# 2164_svf_breakout_planes.net
KiCad netlist of a schematic drawn in EAGLE
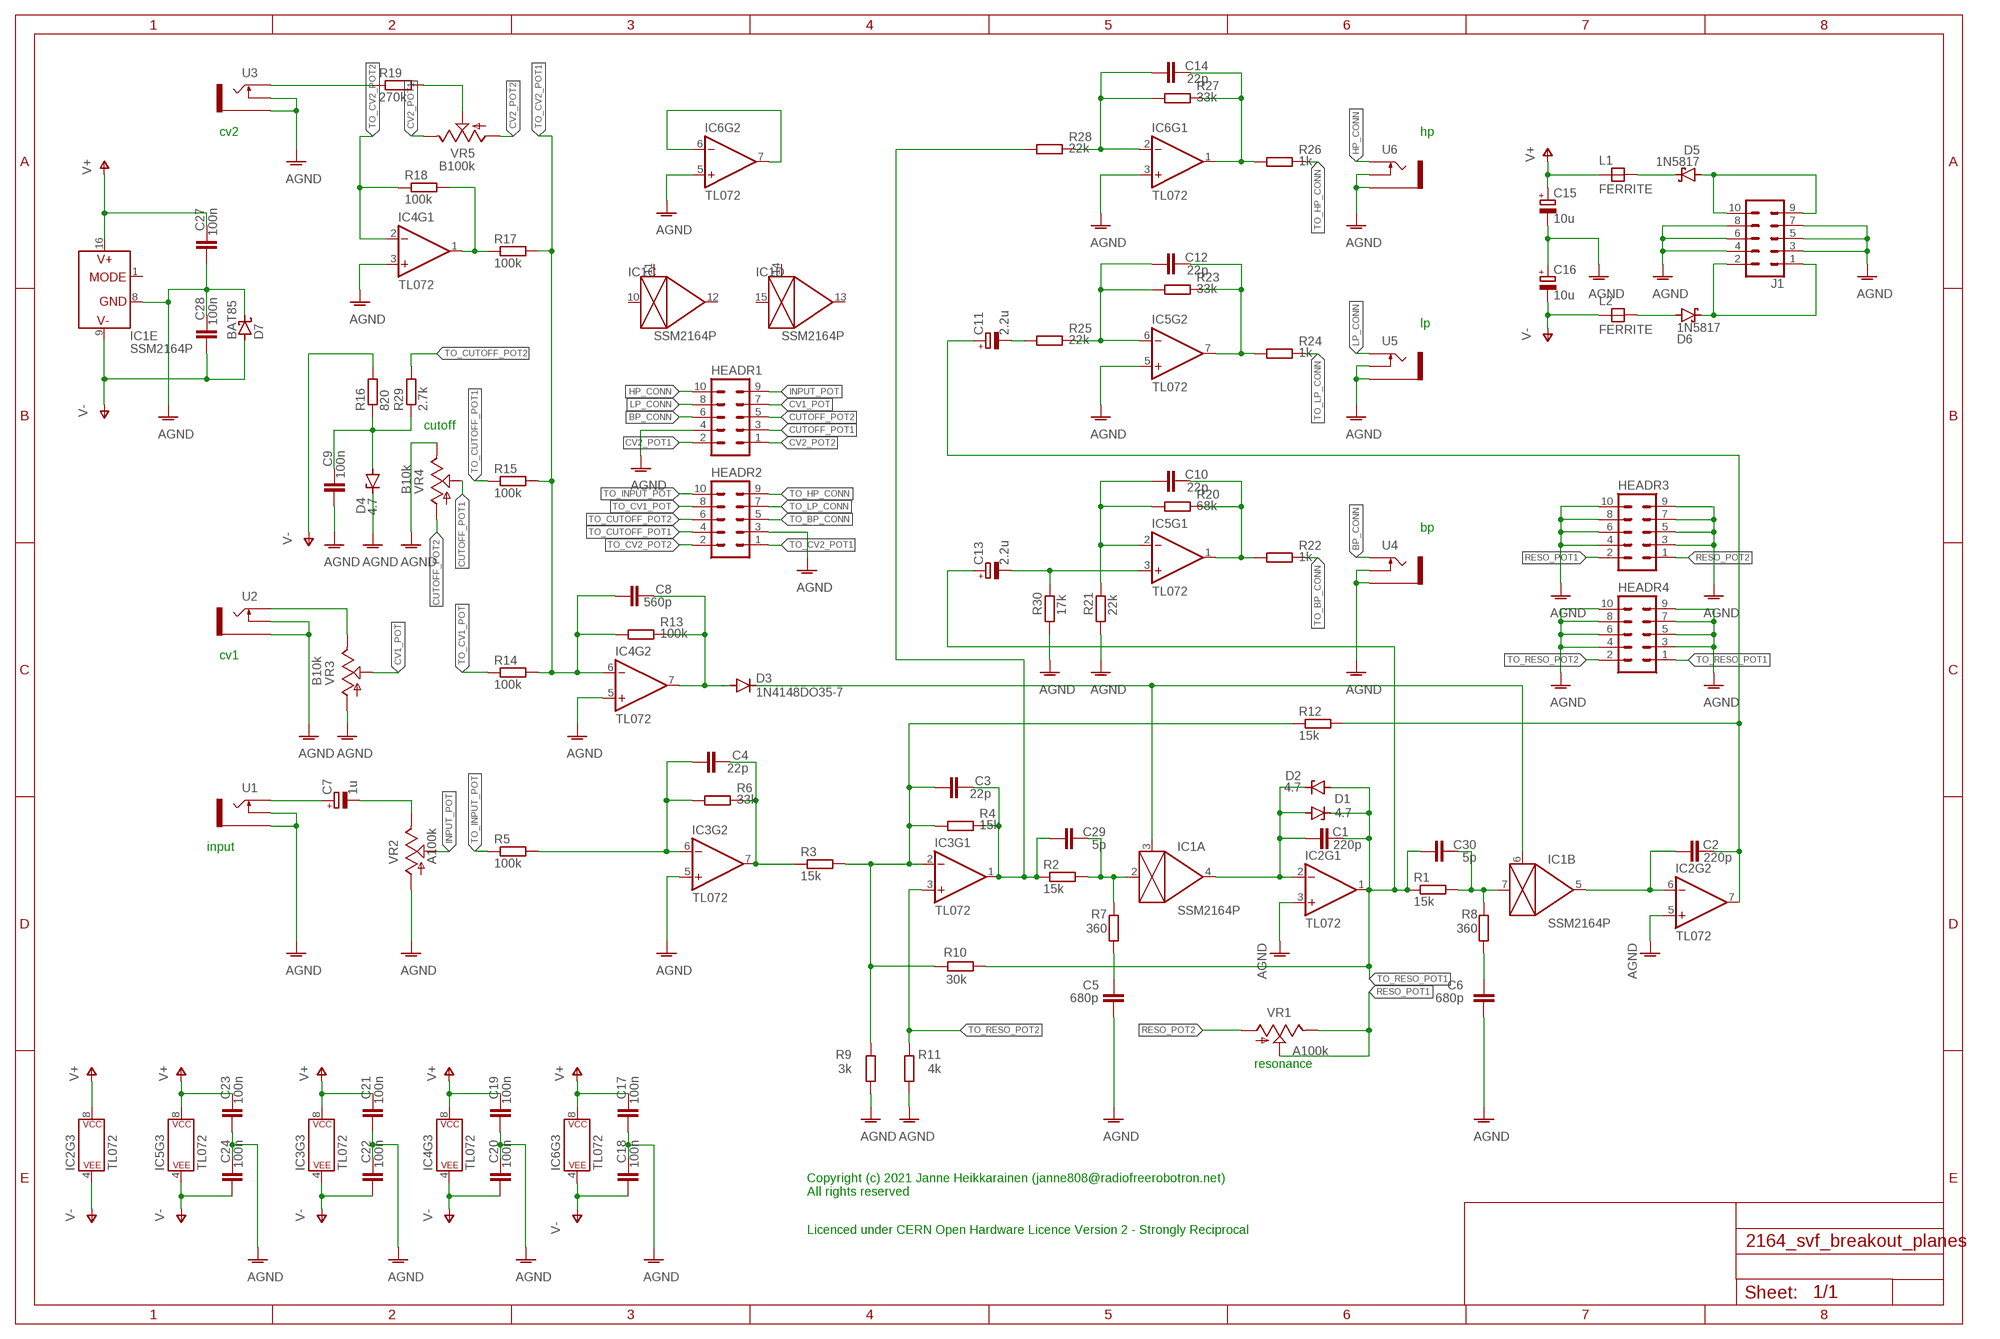
[diagram p0: schematic, sheet 1]

(export (version "E")
  (design (tool "Eeschema 10.0.6"))
  (components
    (comp (ref "C1")
      (value "220p")
      (footprint "eagle-import:C050-025X075")
      (libsource (lib "eagle-import") (part "C-EU050-025X075"))
    )
    (comp (ref "C2")
      (value "220p")
      (footprint "eagle-import:C050-025X075")
      (libsource (lib "eagle-import") (part "C-EU050-025X075"))
    )
    (comp (ref "C3")
      (value "22p")
      (footprint "eagle-import:C050-025X075")
      (libsource (lib "eagle-import") (part "C-EU050-025X075"))
    )
    (comp (ref "C4")
      (value "22p")
      (footprint "eagle-import:C050-025X075")
      (libsource (lib "eagle-import") (part "C-EU050-025X075"))
    )
    (comp (ref "C5")
      (value "680p")
      (footprint "eagle-import:C050-025X075")
      (libsource (lib "eagle-import") (part "C-EU050-025X075"))
    )
    (comp (ref "C6")
      (value "680p")
      (footprint "eagle-import:C050-025X075")
      (libsource (lib "eagle-import") (part "C-EU050-025X075"))
    )
    (comp (ref "C7")
      (value "1u")
      (footprint "eagle-import:E2,5-6E")
      (libsource (lib "eagle-import") (part "CPOL-EUE2,5-6E"))
    )
    (comp (ref "C8")
      (value "560p")
      (footprint "eagle-import:C050-025X075")
      (libsource (lib "eagle-import") (part "C-EU050-025X075"))
    )
    (comp (ref "C9")
      (value "100n")
      (footprint "eagle-import:C050-025X075")
      (libsource (lib "eagle-import") (part "C-EU050-025X075"))
    )
    (comp (ref "C10")
      (value "22p")
      (footprint "eagle-import:C050-025X075")
      (libsource (lib "eagle-import") (part "C-EU050-025X075"))
    )
    (comp (ref "C11")
      (value "2.2u")
      (footprint "eagle-import:E2,5-6E")
      (libsource (lib "eagle-import") (part "CPOL-EUE2,5-6E"))
    )
    (comp (ref "C12")
      (value "22p")
      (footprint "eagle-import:C050-025X075")
      (libsource (lib "eagle-import") (part "C-EU050-025X075"))
    )
    (comp (ref "C13")
      (value "2.2u")
      (footprint "eagle-import:E2,5-6E")
      (libsource (lib "eagle-import") (part "CPOL-EUE2,5-6E"))
    )
    (comp (ref "C14")
      (value "22p")
      (footprint "eagle-import:C050-025X075")
      (libsource (lib "eagle-import") (part "C-EU050-025X075"))
    )
    (comp (ref "C15")
      (value "10u")
      (footprint "eagle-import:E2,5-6E")
      (libsource (lib "eagle-import") (part "CPOL-EUE2,5-6E"))
    )
    (comp (ref "C16")
      (value "10u")
      (footprint "eagle-import:E2,5-6E")
      (libsource (lib "eagle-import") (part "CPOL-EUE2,5-6E"))
    )
    (comp (ref "C17")
      (value "100n")
      (footprint "eagle-import:C050-025X075")
      (libsource (lib "eagle-import") (part "C-EU050-025X075"))
    )
    (comp (ref "C18")
      (value "100n")
      (footprint "eagle-import:C050-025X075")
      (libsource (lib "eagle-import") (part "C-EU050-025X075"))
    )
    (comp (ref "C19")
      (value "100n")
      (footprint "eagle-import:C050-025X075")
      (libsource (lib "eagle-import") (part "C-EU050-025X075"))
    )
    (comp (ref "C20")
      (value "100n")
      (footprint "eagle-import:C050-025X075")
      (libsource (lib "eagle-import") (part "C-EU050-025X075"))
    )
    (comp (ref "C21")
      (value "100n")
      (footprint "eagle-import:C050-025X075")
      (libsource (lib "eagle-import") (part "C-EU050-025X075"))
    )
    (comp (ref "C22")
      (value "100n")
      (footprint "eagle-import:C050-025X075")
      (libsource (lib "eagle-import") (part "C-EU050-025X075"))
    )
    (comp (ref "C23")
      (value "100n")
      (footprint "eagle-import:C050-025X075")
      (libsource (lib "eagle-import") (part "C-EU050-025X075"))
    )
    (comp (ref "C24")
      (value "100n")
      (footprint "eagle-import:C050-025X075")
      (libsource (lib "eagle-import") (part "C-EU050-025X075"))
    )
    (comp (ref "C27")
      (value "100n")
      (footprint "eagle-import:C050-025X075")
      (libsource (lib "eagle-import") (part "C-EU050-025X075"))
    )
    (comp (ref "C28")
      (value "100n")
      (footprint "eagle-import:C050-025X075")
      (libsource (lib "eagle-import") (part "C-EU050-025X075"))
    )
    (comp (ref "C29")
      (value "5p")
      (footprint "eagle-import:C050-025X075")
      (libsource (lib "eagle-import") (part "C-EU050-025X075"))
    )
    (comp (ref "C30")
      (value "5p")
      (footprint "eagle-import:C050-025X075")
      (libsource (lib "eagle-import") (part "C-EU050-025X075"))
    )
    (comp (ref "D1")
      (value "4.7")
      (footprint "eagle-import:DO34Z7")
      (libsource (lib "eagle-import") (part "ZENER-DIODEDO34-7"))
    )
    (comp (ref "D2")
      (value "4.7")
      (footprint "eagle-import:DO34Z7")
      (libsource (lib "eagle-import") (part "ZENER-DIODEDO34-7"))
    )
    (comp (ref "D3")
      (value "1N4148DO35-7")
      (footprint "eagle-import:DO35-7")
      (libsource (lib "eagle-import") (part "1N4148DO35-7"))
    )
    (comp (ref "D4")
      (value "4.7")
      (footprint "eagle-import:DO34Z7")
      (libsource (lib "eagle-import") (part "ZENER-DIODEDO34-7"))
    )
    (comp (ref "D5")
      (value "1N5817")
      (footprint "eagle-import:DO35-7")
      (libsource (lib "eagle-import") (part "SCHOTTKY-DIODEDO35-7"))
    )
    (comp (ref "D6")
      (value "1N5817")
      (footprint "eagle-import:DO35-7")
      (libsource (lib "eagle-import") (part "SCHOTTKY-DIODEDO35-7"))
    )
    (comp (ref "D7")
      (value "BAT85")
      (footprint "eagle-import:DO35-7")
      (libsource (lib "eagle-import") (part "SCHOTTKY-DIODEDO35-7"))
    )
    (comp (ref "HEADR1")
      (value "10PIN_BACKSIDE")
      (footprint "eagle-import:10PIN_BACKSIDE")
      (libsource (lib "eagle-import") (part "10PIN_BACKSIDE"))
    )
    (comp (ref "HEADR2")
      (value "10PIN_BACKSIDE")
      (footprint "eagle-import:10PIN_BACKSIDE")
      (libsource (lib "eagle-import") (part "10PIN_BACKSIDE"))
    )
    (comp (ref "HEADR3")
      (value "10PIN_BACKSIDE")
      (footprint "eagle-import:10PIN_BACKSIDE")
      (libsource (lib "eagle-import") (part "10PIN_BACKSIDE"))
    )
    (comp (ref "HEADR4")
      (value "10PIN_BACKSIDE")
      (footprint "eagle-import:10PIN_BACKSIDE")
      (libsource (lib "eagle-import") (part "10PIN_BACKSIDE"))
    )
    (comp (ref "IC1")
      (value "SSM2164P")
      (footprint "eagle-import:DIL16")
      (libsource (lib "eagle-import") (part "SSM2164P"))
    )
    (comp (ref "IC2")
      (value "TL072")
      (footprint "eagle-import:DIP08")
      (libsource (lib "eagle-import") (part "OPAMP-DUALDIP"))
    )
    (comp (ref "IC3")
      (value "TL072")
      (footprint "eagle-import:DIP08")
      (libsource (lib "eagle-import") (part "OPAMP-DUALDIP"))
    )
    (comp (ref "IC4")
      (value "TL072")
      (footprint "eagle-import:DIP08")
      (libsource (lib "eagle-import") (part "OPAMP-DUALDIP"))
    )
    (comp (ref "IC5")
      (value "TL072")
      (footprint "eagle-import:DIP08")
      (libsource (lib "eagle-import") (part "OPAMP-DUALDIP"))
    )
    (comp (ref "IC6")
      (value "TL072")
      (footprint "eagle-import:DIP08")
      (libsource (lib "eagle-import") (part "OPAMP-DUALDIP"))
    )
    (comp (ref "J1")
      (value "CONN_05X2SHD")
      (footprint "eagle-import:2X5-SHROUDED")
      (libsource (lib "eagle-import") (part "CONN_05X2SHD"))
    )
    (comp (ref "L1")
      (value "FERRITE")
      (footprint "eagle-import:FB-085")
      (libsource (lib "eagle-import") (part "FB-085"))
    )
    (comp (ref "L2")
      (value "FERRITE")
      (footprint "eagle-import:FB-085")
      (libsource (lib "eagle-import") (part "FB-085"))
    )
    (comp (ref "R1")
      (value "15k")
      (footprint "eagle-import:0207_2V")
      (libsource (lib "eagle-import") (part "R-EU_0207/2V"))
    )
    (comp (ref "R2")
      (value "15k")
      (footprint "eagle-import:0207_2V")
      (libsource (lib "eagle-import") (part "R-EU_0207/2V"))
    )
    (comp (ref "R3")
      (value "15k")
      (footprint "eagle-import:0207_2V")
      (libsource (lib "eagle-import") (part "R-EU_0207/2V"))
    )
    (comp (ref "R4")
      (value "15k")
      (footprint "eagle-import:0207_2V")
      (libsource (lib "eagle-import") (part "R-EU_0207/2V"))
    )
    (comp (ref "R5")
      (value "100k")
      (footprint "eagle-import:0207_2V")
      (libsource (lib "eagle-import") (part "R-EU_0207/2V"))
    )
    (comp (ref "R6")
      (value "33k")
      (footprint "eagle-import:0207_2V")
      (libsource (lib "eagle-import") (part "R-EU_0207/2V"))
    )
    (comp (ref "R7")
      (value "360")
      (footprint "eagle-import:0207_2V")
      (libsource (lib "eagle-import") (part "R-EU_0207/2V"))
    )
    (comp (ref "R8")
      (value "360")
      (footprint "eagle-import:0207_2V")
      (libsource (lib "eagle-import") (part "R-EU_0207/2V"))
    )
    (comp (ref "R9")
      (value "3k")
      (footprint "eagle-import:0207_2V")
      (libsource (lib "eagle-import") (part "R-EU_0207/2V"))
    )
    (comp (ref "R10")
      (value "30k")
      (footprint "eagle-import:0207_2V")
      (libsource (lib "eagle-import") (part "R-EU_0207/2V"))
    )
    (comp (ref "R11")
      (value "4k")
      (footprint "eagle-import:0207_2V")
      (libsource (lib "eagle-import") (part "R-EU_0207/2V"))
    )
    (comp (ref "R12")
      (value "15k")
      (footprint "eagle-import:0207_2V")
      (libsource (lib "eagle-import") (part "R-EU_0207/2V"))
    )
    (comp (ref "R13")
      (value "100k")
      (footprint "eagle-import:0207_2V")
      (libsource (lib "eagle-import") (part "R-EU_0207/2V"))
    )
    (comp (ref "R14")
      (value "100k")
      (footprint "eagle-import:0207_2V")
      (libsource (lib "eagle-import") (part "R-EU_0207/2V"))
    )
    (comp (ref "R15")
      (value "100k")
      (footprint "eagle-import:0207_2V")
      (libsource (lib "eagle-import") (part "R-EU_0207/2V"))
    )
    (comp (ref "R16")
      (value "820")
      (footprint "eagle-import:0207_2V")
      (libsource (lib "eagle-import") (part "R-EU_0207/2V"))
    )
    (comp (ref "R17")
      (value "100k")
      (footprint "eagle-import:0207_2V")
      (libsource (lib "eagle-import") (part "R-EU_0207/2V"))
    )
    (comp (ref "R18")
      (value "100k")
      (footprint "eagle-import:0207_2V")
      (libsource (lib "eagle-import") (part "R-EU_0207/2V"))
    )
    (comp (ref "R19")
      (value "270k")
      (footprint "eagle-import:0207_2V")
      (libsource (lib "eagle-import") (part "R-EU_0207/2V"))
    )
    (comp (ref "R20")
      (value "68k")
      (footprint "eagle-import:0207_2V")
      (libsource (lib "eagle-import") (part "R-EU_0207/2V"))
    )
    (comp (ref "R21")
      (value "22k")
      (footprint "eagle-import:0207_2V")
      (libsource (lib "eagle-import") (part "R-EU_0207/2V"))
    )
    (comp (ref "R22")
      (value "1k")
      (footprint "eagle-import:0207_2V")
      (libsource (lib "eagle-import") (part "R-EU_0207/2V"))
    )
    (comp (ref "R23")
      (value "33k")
      (footprint "eagle-import:0207_2V")
      (libsource (lib "eagle-import") (part "R-EU_0207/2V"))
    )
    (comp (ref "R24")
      (value "1k")
      (footprint "eagle-import:0207_2V")
      (libsource (lib "eagle-import") (part "R-EU_0207/2V"))
    )
    (comp (ref "R25")
      (value "22k")
      (footprint "eagle-import:0207_2V")
      (libsource (lib "eagle-import") (part "R-EU_0207/2V"))
    )
    (comp (ref "R26")
      (value "1k")
      (footprint "eagle-import:0207_2V")
      (libsource (lib "eagle-import") (part "R-EU_0207/2V"))
    )
    (comp (ref "R27")
      (value "33k")
      (footprint "eagle-import:0207_2V")
      (libsource (lib "eagle-import") (part "R-EU_0207/2V"))
    )
    (comp (ref "R28")
      (value "22k")
      (footprint "eagle-import:0207_2V")
      (libsource (lib "eagle-import") (part "R-EU_0207/2V"))
    )
    (comp (ref "R29")
      (value "2.7k")
      (footprint "eagle-import:0207_2V")
      (libsource (lib "eagle-import") (part "R-EU_0207/2V"))
    )
    (comp (ref "R30")
      (value "17k")
      (footprint "eagle-import:0207_2V")
      (libsource (lib "eagle-import") (part "R-EU_0207/2V"))
    )
    (comp (ref "U1")
      (value "THONKICONNNEW")
      (footprint "eagle-import:WQP-PJ301M-12_JACK")
      (libsource (lib "eagle-import") (part "THONKICONNNEW"))
    )
    (comp (ref "U2")
      (value "THONKICONNNEW")
      (footprint "eagle-import:WQP-PJ301M-12_JACK")
      (libsource (lib "eagle-import") (part "THONKICONNNEW"))
    )
    (comp (ref "U3")
      (value "THONKICONNNEW")
      (footprint "eagle-import:WQP-PJ301M-12_JACK")
      (libsource (lib "eagle-import") (part "THONKICONNNEW"))
    )
    (comp (ref "U4")
      (value "THONKICONNNEW")
      (footprint "eagle-import:WQP-PJ301M-12_JACK")
      (libsource (lib "eagle-import") (part "THONKICONNNEW"))
    )
    (comp (ref "U5")
      (value "THONKICONNNEW")
      (footprint "eagle-import:WQP-PJ301M-12_JACK")
      (libsource (lib "eagle-import") (part "THONKICONNNEW"))
    )
    (comp (ref "U6")
      (value "THONKICONNNEW")
      (footprint "eagle-import:WQP-PJ301M-12_JACK")
      (libsource (lib "eagle-import") (part "THONKICONNNEW"))
    )
    (comp (ref "VR1")
      (value "A100k")
      (footprint "eagle-import:9MM_SNAP-IN_POT")
      (libsource (lib "eagle-import") (part "9MM_SNAP-IN_POT_"))
    )
    (comp (ref "VR2")
      (value "A100k")
      (footprint "eagle-import:9MM_SNAP-IN_POT")
      (libsource (lib "eagle-import") (part "9MM_SNAP-IN_POT_"))
    )
    (comp (ref "VR3")
      (value "B10k")
      (footprint "eagle-import:9MM_SNAP-IN_POT")
      (libsource (lib "eagle-import") (part "9MM_SNAP-IN_POT_"))
    )
    (comp (ref "VR4")
      (value "B10k")
      (footprint "eagle-import:9MM_SNAP-IN_POT")
      (libsource (lib "eagle-import") (part "9MM_SNAP-IN_POT_"))
    )
    (comp (ref "VR5")
      (value "B100k")
      (footprint "eagle-import:9MM_SNAP-IN_POT")
      (libsource (lib "eagle-import") (part "9MM_SNAP-IN_POT_"))
    )
  )
  (nets
    (net (code "1") (name "AGND") (class "Default")
      (node (ref "C15") (pin "-") (pinfunction "-_-") (pintype "passive"))
      (node (ref "C16") (pin "+") (pinfunction "+_+") (pintype "passive"))
      (node (ref "C17") (pin "1") (pinfunction "1_1") (pintype "passive"))
      (node (ref "C18") (pin "2") (pinfunction "2_2") (pintype "passive"))
      (node (ref "C19") (pin "1") (pinfunction "1_1") (pintype "passive"))
      (node (ref "C20") (pin "2") (pinfunction "2_2") (pintype "passive"))
      (node (ref "C21") (pin "1") (pinfunction "1_1") (pintype "passive"))
      (node (ref "C22") (pin "2") (pinfunction "2_2") (pintype "passive"))
      (node (ref "C23") (pin "1") (pinfunction "1_1") (pintype "passive"))
      (node (ref "C24") (pin "2") (pinfunction "2_2") (pintype "passive"))
      (node (ref "C27") (pin "1") (pinfunction "1_1") (pintype "passive"))
      (node (ref "C28") (pin "2") (pinfunction "2_2") (pintype "passive"))
      (node (ref "C5") (pin "1") (pinfunction "1_1") (pintype "passive"))
      (node (ref "C6") (pin "1") (pinfunction "1_1") (pintype "passive"))
      (node (ref "C9") (pin "1") (pinfunction "1_1") (pintype "passive"))
      (node (ref "D4") (pin "C") (pinfunction "C_C") (pintype "passive"))
      (node (ref "D7") (pin "C") (pinfunction "C_C") (pintype "passive"))
      (node (ref "HEADR1") (pin "4") (pinfunction "4_4") (pintype "passive"))
      (node (ref "HEADR2") (pin "3") (pinfunction "3_3") (pintype "passive"))
      (node (ref "HEADR3") (pin "10") (pinfunction "10_10") (pintype "passive"))
      (node (ref "HEADR3") (pin "3") (pinfunction "3_3") (pintype "passive"))
      (node (ref "HEADR3") (pin "4") (pinfunction "4_4") (pintype "passive"))
      (node (ref "HEADR3") (pin "5") (pinfunction "5_5") (pintype "passive"))
      (node (ref "HEADR3") (pin "6") (pinfunction "6_6") (pintype "passive"))
      (node (ref "HEADR3") (pin "7") (pinfunction "7_7") (pintype "passive"))
      (node (ref "HEADR3") (pin "8") (pinfunction "8_8") (pintype "passive"))
      (node (ref "HEADR3") (pin "9") (pinfunction "9_9") (pintype "passive"))
      (node (ref "HEADR4") (pin "10") (pinfunction "10_10") (pintype "passive"))
      (node (ref "HEADR4") (pin "3") (pinfunction "3_3") (pintype "passive"))
      (node (ref "HEADR4") (pin "4") (pinfunction "4_4") (pintype "passive"))
      (node (ref "HEADR4") (pin "5") (pinfunction "5_5") (pintype "passive"))
      (node (ref "HEADR4") (pin "6") (pinfunction "6_6") (pintype "passive"))
      (node (ref "HEADR4") (pin "7") (pinfunction "7_7") (pintype "passive"))
      (node (ref "HEADR4") (pin "8") (pinfunction "8_8") (pintype "passive"))
      (node (ref "HEADR4") (pin "9") (pinfunction "9_9") (pintype "passive"))
      (node (ref "IC1") (pin "8") (pinfunction "GND_8") (pintype "power_in"))
      (node (ref "IC2") (pin "3") (pinfunction "+IN_3") (pintype "input"))
      (node (ref "IC2") (pin "5") (pinfunction "+IN_5") (pintype "input"))
      (node (ref "IC3") (pin "5") (pinfunction "+IN_5") (pintype "input"))
      (node (ref "IC4") (pin "3") (pinfunction "+IN_3") (pintype "input"))
      (node (ref "IC4") (pin "5") (pinfunction "+IN_5") (pintype "input"))
      (node (ref "IC5") (pin "5") (pinfunction "+IN_5") (pintype "input"))
      (node (ref "IC6") (pin "3") (pinfunction "+IN_3") (pintype "input"))
      (node (ref "IC6") (pin "5") (pinfunction "+IN_5") (pintype "input"))
      (node (ref "J1") (pin "3") (pinfunction "3_3") (pintype "passive"))
      (node (ref "J1") (pin "4") (pinfunction "4_4") (pintype "passive"))
      (node (ref "J1") (pin "5") (pinfunction "5_5") (pintype "passive"))
      (node (ref "J1") (pin "6") (pinfunction "6_6") (pintype "passive"))
      (node (ref "J1") (pin "7") (pinfunction "7_7") (pintype "passive"))
      (node (ref "J1") (pin "8") (pinfunction "8_8") (pintype "passive"))
      (node (ref "R11") (pin "1") (pinfunction "1_1") (pintype "passive"))
      (node (ref "R21") (pin "1") (pinfunction "1_1") (pintype "passive"))
      (node (ref "R30") (pin "1") (pinfunction "1_1") (pintype "passive"))
      (node (ref "R9") (pin "1") (pinfunction "1_1") (pintype "passive"))
      (node (ref "U1") (pin "P$2_SWITCH") (pinfunction "SWITCH_P$2_SWITCH") (pintype "passive"))
      (node (ref "U1") (pin "P$3_SLEEVE") (pinfunction "SLEEVE_P$3_SLEEVE") (pintype "passive"))
      (node (ref "U2") (pin "P$2_SWITCH") (pinfunction "SWITCH_P$2_SWITCH") (pintype "passive"))
      (node (ref "U2") (pin "P$3_SLEEVE") (pinfunction "SLEEVE_P$3_SLEEVE") (pintype "passive"))
      (node (ref "U3") (pin "P$2_SWITCH") (pinfunction "SWITCH_P$2_SWITCH") (pintype "passive"))
      (node (ref "U3") (pin "P$3_SLEEVE") (pinfunction "SLEEVE_P$3_SLEEVE") (pintype "passive"))
      (node (ref "U4") (pin "P$2_SWITCH") (pinfunction "SWITCH_P$2_SWITCH") (pintype "passive"))
      (node (ref "U4") (pin "P$3_SLEEVE") (pinfunction "SLEEVE_P$3_SLEEVE") (pintype "passive"))
      (node (ref "U5") (pin "P$2_SWITCH") (pinfunction "SWITCH_P$2_SWITCH") (pintype "passive"))
      (node (ref "U5") (pin "P$3_SLEEVE") (pinfunction "SLEEVE_P$3_SLEEVE") (pintype "passive"))
      (node (ref "U6") (pin "P$2_SWITCH") (pinfunction "SWITCH_P$2_SWITCH") (pintype "passive"))
      (node (ref "U6") (pin "P$3_SLEEVE") (pinfunction "SLEEVE_P$3_SLEEVE") (pintype "passive"))
      (node (ref "VR2") (pin "1") (pinfunction "A_1") (pintype "passive"))
      (node (ref "VR3") (pin "1") (pinfunction "A_1") (pintype "passive"))
      (node (ref "VR4") (pin "3") (pinfunction "E_3") (pintype "passive"))
    )
    (net (code "2") (name "BP_CONN") (class "Default")
      (node (ref "HEADR1") (pin "6") (pinfunction "6_6") (pintype "passive"))
      (node (ref "U4") (pin "P$1_TIP") (pinfunction "TIP_P$1_TIP") (pintype "passive"))
    )
    (net (code "3") (name "CUTOFF_POT1") (class "Default")
      (node (ref "HEADR1") (pin "3") (pinfunction "3_3") (pintype "passive"))
      (node (ref "VR4") (pin "2") (pinfunction "S_2") (pintype "passive"))
    )
    (net (code "4") (name "CUTOFF_POT2") (class "Default")
      (node (ref "HEADR1") (pin "5") (pinfunction "5_5") (pintype "passive"))
      (node (ref "VR4") (pin "1") (pinfunction "A_1") (pintype "passive"))
    )
    (net (code "5") (name "CV1_POT") (class "Default")
      (node (ref "HEADR1") (pin "7") (pinfunction "7_7") (pintype "passive"))
      (node (ref "VR3") (pin "2") (pinfunction "S_2") (pintype "passive"))
    )
    (net (code "6") (name "CV2_POT1") (class "Default")
      (node (ref "HEADR1") (pin "2") (pinfunction "2_2") (pintype "passive"))
      (node (ref "VR5") (pin "3") (pinfunction "E_3") (pintype "passive"))
    )
    (net (code "7") (name "CV2_POT2") (class "Default")
      (node (ref "HEADR1") (pin "1") (pinfunction "1_1") (pintype "passive"))
      (node (ref "VR5") (pin "1") (pinfunction "A_1") (pintype "passive"))
    )
    (net (code "8") (name "HP_CONN") (class "Default")
      (node (ref "HEADR1") (pin "10") (pinfunction "10_10") (pintype "passive"))
      (node (ref "U6") (pin "P$1_TIP") (pinfunction "TIP_P$1_TIP") (pintype "passive"))
    )
    (net (code "9") (name "INPUT_POT") (class "Default")
      (node (ref "HEADR1") (pin "9") (pinfunction "9_9") (pintype "passive"))
      (node (ref "VR2") (pin "2") (pinfunction "S_2") (pintype "passive"))
    )
    (net (code "10") (name "LP_CONN") (class "Default")
      (node (ref "HEADR1") (pin "8") (pinfunction "8_8") (pintype "passive"))
      (node (ref "U5") (pin "P$1_TIP") (pinfunction "TIP_P$1_TIP") (pintype "passive"))
    )
    (net (code "11") (name "Net-(C5-Pad2)") (class "Default")
      (node (ref "C5") (pin "2") (pinfunction "2_2") (pintype "passive"))
      (node (ref "R7") (pin "1") (pinfunction "1_1") (pintype "passive"))
    )
    (net (code "12") (name "Net-(C6-Pad2)") (class "Default")
      (node (ref "C6") (pin "2") (pinfunction "2_2") (pintype "passive"))
      (node (ref "R8") (pin "1") (pinfunction "1_1") (pintype "passive"))
    )
    (net (code "13") (name "Net-(C9-Pad2)") (class "Default")
      (node (ref "C9") (pin "2") (pinfunction "2_2") (pintype "passive"))
      (node (ref "D4") (pin "A") (pinfunction "A_A") (pintype "passive"))
      (node (ref "R16") (pin "1") (pinfunction "1_1") (pintype "passive"))
      (node (ref "R29") (pin "1") (pinfunction "1_1") (pintype "passive"))
    )
    (net (code "14") (name "Net-(C11-Pad-)") (class "Default")
      (node (ref "C11") (pin "-") (pinfunction "-_-") (pintype "passive"))
      (node (ref "R25") (pin "1") (pinfunction "1_1") (pintype "passive"))
    )
    (net (code "15") (name "Net-(D5-PadA)") (class "Default")
      (node (ref "D5") (pin "A") (pinfunction "A_A") (pintype "passive"))
      (node (ref "J1") (pin "10") (pinfunction "10_10") (pintype "passive"))
      (node (ref "J1") (pin "9") (pinfunction "9_9") (pintype "passive"))
    )
    (net (code "16") (name "Net-(D5-PadC)") (class "Default")
      (node (ref "D5") (pin "C") (pinfunction "C_C") (pintype "passive"))
      (node (ref "L1") (pin "2") (pinfunction "2_2") (pintype "passive"))
    )
    (net (code "17") (name "Net-(D6-PadA)") (class "Default")
      (node (ref "D6") (pin "A") (pinfunction "A_A") (pintype "passive"))
      (node (ref "L2") (pin "2") (pinfunction "2_2") (pintype "passive"))
    )
    (net (code "18") (name "Net-(D6-PadC)") (class "Default")
      (node (ref "D6") (pin "C") (pinfunction "C_C") (pintype "passive"))
      (node (ref "J1") (pin "1") (pinfunction "1_1") (pintype "passive"))
      (node (ref "J1") (pin "2") (pinfunction "2_2") (pintype "passive"))
    )
    (net (code "19") (name "Net-(IC1A-CTRL)") (class "Default")
      (node (ref "D3") (pin "C") (pinfunction "C_C") (pintype "passive"))
      (node (ref "IC1") (pin "3") (pinfunction "CTRL_3") (pintype "input"))
      (node (ref "IC1") (pin "6") (pinfunction "CTRL_6") (pintype "input"))
    )
    (net (code "20") (name "Net-(IC1A-IN)") (class "Default")
      (node (ref "C29") (pin "2") (pinfunction "2_2") (pintype "passive"))
      (node (ref "IC1") (pin "2") (pinfunction "IN_2") (pintype "input"))
      (node (ref "R2") (pin "2") (pinfunction "2_2") (pintype "passive"))
      (node (ref "R7") (pin "2") (pinfunction "2_2") (pintype "passive"))
    )
    (net (code "21") (name "Net-(IC1A-OUT)") (class "Default")
      (node (ref "C1") (pin "1") (pinfunction "1_1") (pintype "passive"))
      (node (ref "D1") (pin "A") (pinfunction "A_A") (pintype "passive"))
      (node (ref "D2") (pin "C") (pinfunction "C_C") (pintype "passive"))
      (node (ref "IC1") (pin "4") (pinfunction "OUT_4") (pintype "output"))
      (node (ref "IC2") (pin "2") (pinfunction "-IN_2") (pintype "input"))
    )
    (net (code "22") (name "Net-(IC1B-IN)") (class "Default")
      (node (ref "C30") (pin "2") (pinfunction "2_2") (pintype "passive"))
      (node (ref "IC1") (pin "7") (pinfunction "IN_7") (pintype "input"))
      (node (ref "R1") (pin "2") (pinfunction "2_2") (pintype "passive"))
      (node (ref "R8") (pin "2") (pinfunction "2_2") (pintype "passive"))
    )
    (net (code "23") (name "Net-(IC1B-OUT)") (class "Default")
      (node (ref "C2") (pin "1") (pinfunction "1_1") (pintype "passive"))
      (node (ref "IC1") (pin "5") (pinfunction "OUT_5") (pintype "output"))
      (node (ref "IC2") (pin "6") (pinfunction "-IN_6") (pintype "input"))
    )
    (net (code "24") (name "Net-(IC2B-OUT)") (class "Default")
      (node (ref "C11") (pin "+") (pinfunction "+_+") (pintype "passive"))
      (node (ref "C2") (pin "2") (pinfunction "2_2") (pintype "passive"))
      (node (ref "IC2") (pin "7") (pinfunction "OUT_7") (pintype "output"))
      (node (ref "R12") (pin "2") (pinfunction "2_2") (pintype "passive"))
    )
    (net (code "25") (name "Net-(IC3A--IN)") (class "Default")
      (node (ref "C3") (pin "1") (pinfunction "1_1") (pintype "passive"))
      (node (ref "IC3") (pin "2") (pinfunction "-IN_2") (pintype "input"))
      (node (ref "R10") (pin "2") (pinfunction "2_2") (pintype "passive"))
      (node (ref "R12") (pin "1") (pinfunction "1_1") (pintype "passive"))
      (node (ref "R3") (pin "2") (pinfunction "2_2") (pintype "passive"))
      (node (ref "R4") (pin "1") (pinfunction "1_1") (pintype "passive"))
      (node (ref "R9") (pin "2") (pinfunction "2_2") (pintype "passive"))
    )
    (net (code "26") (name "Net-(IC3A-OUT)") (class "Default")
      (node (ref "C29") (pin "1") (pinfunction "1_1") (pintype "passive"))
      (node (ref "C3") (pin "2") (pinfunction "2_2") (pintype "passive"))
      (node (ref "IC3") (pin "1") (pinfunction "OUT_1") (pintype "output"))
      (node (ref "R2") (pin "1") (pinfunction "1_1") (pintype "passive"))
      (node (ref "R28") (pin "1") (pinfunction "1_1") (pintype "passive"))
      (node (ref "R4") (pin "2") (pinfunction "2_2") (pintype "passive"))
    )
    (net (code "27") (name "Net-(IC3B--IN)") (class "Default")
      (node (ref "C4") (pin "1") (pinfunction "1_1") (pintype "passive"))
      (node (ref "IC3") (pin "6") (pinfunction "-IN_6") (pintype "input"))
      (node (ref "R5") (pin "2") (pinfunction "2_2") (pintype "passive"))
      (node (ref "R6") (pin "1") (pinfunction "1_1") (pintype "passive"))
    )
    (net (code "28") (name "Net-(IC3B-OUT)") (class "Default")
      (node (ref "C4") (pin "2") (pinfunction "2_2") (pintype "passive"))
      (node (ref "IC3") (pin "7") (pinfunction "OUT_7") (pintype "output"))
      (node (ref "R3") (pin "1") (pinfunction "1_1") (pintype "passive"))
      (node (ref "R6") (pin "2") (pinfunction "2_2") (pintype "passive"))
    )
    (net (code "29") (name "Net-(IC4A-OUT)") (class "Default")
      (node (ref "IC4") (pin "1") (pinfunction "OUT_1") (pintype "output"))
      (node (ref "R17") (pin "1") (pinfunction "1_1") (pintype "passive"))
      (node (ref "R18") (pin "2") (pinfunction "2_2") (pintype "passive"))
    )
    (net (code "30") (name "Net-(IC4B-OUT)") (class "Default")
      (node (ref "C8") (pin "2") (pinfunction "2_2") (pintype "passive"))
      (node (ref "D3") (pin "A") (pinfunction "A_A") (pintype "passive"))
      (node (ref "IC4") (pin "7") (pinfunction "OUT_7") (pintype "output"))
      (node (ref "R13") (pin "2") (pinfunction "2_2") (pintype "passive"))
    )
    (net (code "31") (name "Net-(IC5A-+IN)") (class "Default")
      (node (ref "C13") (pin "-") (pinfunction "-_-") (pintype "passive"))
      (node (ref "IC5") (pin "3") (pinfunction "+IN_3") (pintype "input"))
      (node (ref "R30") (pin "2") (pinfunction "2_2") (pintype "passive"))
    )
    (net (code "32") (name "Net-(IC5A--IN)") (class "Default")
      (node (ref "C10") (pin "1") (pinfunction "1_1") (pintype "passive"))
      (node (ref "IC5") (pin "2") (pinfunction "-IN_2") (pintype "input"))
      (node (ref "R20") (pin "1") (pinfunction "1_1") (pintype "passive"))
      (node (ref "R21") (pin "2") (pinfunction "2_2") (pintype "passive"))
    )
    (net (code "33") (name "Net-(IC5A-OUT)") (class "Default")
      (node (ref "C10") (pin "2") (pinfunction "2_2") (pintype "passive"))
      (node (ref "IC5") (pin "1") (pinfunction "OUT_1") (pintype "output"))
      (node (ref "R20") (pin "2") (pinfunction "2_2") (pintype "passive"))
      (node (ref "R22") (pin "1") (pinfunction "1_1") (pintype "passive"))
    )
    (net (code "34") (name "Net-(IC5B--IN)") (class "Default")
      (node (ref "C12") (pin "1") (pinfunction "1_1") (pintype "passive"))
      (node (ref "IC5") (pin "6") (pinfunction "-IN_6") (pintype "input"))
      (node (ref "R23") (pin "1") (pinfunction "1_1") (pintype "passive"))
      (node (ref "R25") (pin "2") (pinfunction "2_2") (pintype "passive"))
    )
    (net (code "35") (name "Net-(IC5B-OUT)") (class "Default")
      (node (ref "C12") (pin "2") (pinfunction "2_2") (pintype "passive"))
      (node (ref "IC5") (pin "7") (pinfunction "OUT_7") (pintype "output"))
      (node (ref "R23") (pin "2") (pinfunction "2_2") (pintype "passive"))
      (node (ref "R24") (pin "1") (pinfunction "1_1") (pintype "passive"))
    )
    (net (code "36") (name "Net-(IC6A--IN)") (class "Default")
      (node (ref "C14") (pin "1") (pinfunction "1_1") (pintype "passive"))
      (node (ref "IC6") (pin "2") (pinfunction "-IN_2") (pintype "input"))
      (node (ref "R27") (pin "1") (pinfunction "1_1") (pintype "passive"))
      (node (ref "R28") (pin "2") (pinfunction "2_2") (pintype "passive"))
    )
    (net (code "37") (name "Net-(IC6A-OUT)") (class "Default")
      (node (ref "C14") (pin "2") (pinfunction "2_2") (pintype "passive"))
      (node (ref "IC6") (pin "1") (pinfunction "OUT_1") (pintype "output"))
      (node (ref "R26") (pin "1") (pinfunction "1_1") (pintype "passive"))
      (node (ref "R27") (pin "2") (pinfunction "2_2") (pintype "passive"))
    )
    (net (code "38") (name "Net-(IC6B--IN)") (class "Default")
      (node (ref "IC6") (pin "6") (pinfunction "-IN_6") (pintype "input"))
      (node (ref "IC6") (pin "7") (pinfunction "OUT_7") (pintype "output"))
    )
    (net (code "39") (name "Net-(U1-TIP)") (class "Default")
      (node (ref "C7") (pin "+") (pinfunction "+_+") (pintype "passive"))
      (node (ref "U1") (pin "P$1_TIP") (pinfunction "TIP_P$1_TIP") (pintype "passive"))
    )
    (net (code "40") (name "Net-(U2-TIP)") (class "Default")
      (node (ref "U2") (pin "P$1_TIP") (pinfunction "TIP_P$1_TIP") (pintype "passive"))
      (node (ref "VR3") (pin "3") (pinfunction "E_3") (pintype "passive"))
    )
    (net (code "41") (name "Net-(U3-TIP)") (class "Default")
      (node (ref "R19") (pin "1") (pinfunction "1_1") (pintype "passive"))
      (node (ref "U3") (pin "P$1_TIP") (pinfunction "TIP_P$1_TIP") (pintype "passive"))
    )
    (net (code "42") (name "Net-(VR2-E)") (class "Default")
      (node (ref "C7") (pin "-") (pinfunction "-_-") (pintype "passive"))
      (node (ref "VR2") (pin "3") (pinfunction "E_3") (pintype "passive"))
    )
    (net (code "43") (name "Net-(VR5-S)") (class "Default")
      (node (ref "R19") (pin "2") (pinfunction "2_2") (pintype "passive"))
      (node (ref "VR5") (pin "2") (pinfunction "S_2") (pintype "passive"))
    )
    (net (code "44") (name "RESO_POT1") (class "Default")
      (node (ref "HEADR3") (pin "2") (pinfunction "2_2") (pintype "passive"))
      (node (ref "VR1") (pin "2") (pinfunction "S_2") (pintype "passive"))
      (node (ref "VR1") (pin "3") (pinfunction "E_3") (pintype "passive"))
    )
    (net (code "45") (name "RESO_POT2") (class "Default")
      (node (ref "HEADR3") (pin "1") (pinfunction "1_1") (pintype "passive"))
      (node (ref "VR1") (pin "1") (pinfunction "A_1") (pintype "passive"))
    )
    (net (code "46") (name "TO_BP_CONN") (class "Default")
      (node (ref "HEADR2") (pin "5") (pinfunction "5_5") (pintype "passive"))
      (node (ref "R22") (pin "2") (pinfunction "2_2") (pintype "passive"))
    )
    (net (code "47") (name "TO_CUTOFF_POT1") (class "Default")
      (node (ref "HEADR2") (pin "4") (pinfunction "4_4") (pintype "passive"))
      (node (ref "R15") (pin "1") (pinfunction "1_1") (pintype "passive"))
    )
    (net (code "48") (name "TO_CUTOFF_POT2") (class "Default")
      (node (ref "HEADR2") (pin "6") (pinfunction "6_6") (pintype "passive"))
      (node (ref "R29") (pin "2") (pinfunction "2_2") (pintype "passive"))
    )
    (net (code "49") (name "TO_CV1_POT") (class "Default")
      (node (ref "HEADR2") (pin "8") (pinfunction "8_8") (pintype "passive"))
      (node (ref "R14") (pin "1") (pinfunction "1_1") (pintype "passive"))
    )
    (net (code "50") (name "TO_CV2_POT1") (class "Default")
      (node (ref "C8") (pin "1") (pinfunction "1_1") (pintype "passive"))
      (node (ref "HEADR2") (pin "1") (pinfunction "1_1") (pintype "passive"))
      (node (ref "IC4") (pin "6") (pinfunction "-IN_6") (pintype "input"))
      (node (ref "R13") (pin "1") (pinfunction "1_1") (pintype "passive"))
      (node (ref "R14") (pin "2") (pinfunction "2_2") (pintype "passive"))
      (node (ref "R15") (pin "2") (pinfunction "2_2") (pintype "passive"))
      (node (ref "R17") (pin "2") (pinfunction "2_2") (pintype "passive"))
    )
    (net (code "51") (name "TO_CV2_POT2") (class "Default")
      (node (ref "HEADR2") (pin "2") (pinfunction "2_2") (pintype "passive"))
      (node (ref "IC4") (pin "2") (pinfunction "-IN_2") (pintype "input"))
      (node (ref "R18") (pin "1") (pinfunction "1_1") (pintype "passive"))
    )
    (net (code "52") (name "TO_HP_CONN") (class "Default")
      (node (ref "HEADR2") (pin "9") (pinfunction "9_9") (pintype "passive"))
      (node (ref "R26") (pin "2") (pinfunction "2_2") (pintype "passive"))
    )
    (net (code "53") (name "TO_INPUT_POT") (class "Default")
      (node (ref "HEADR2") (pin "10") (pinfunction "10_10") (pintype "passive"))
      (node (ref "R5") (pin "1") (pinfunction "1_1") (pintype "passive"))
    )
    (net (code "54") (name "TO_LP_CONN") (class "Default")
      (node (ref "HEADR2") (pin "7") (pinfunction "7_7") (pintype "passive"))
      (node (ref "R24") (pin "2") (pinfunction "2_2") (pintype "passive"))
    )
    (net (code "55") (name "TO_RESO_POT1") (class "Default")
      (node (ref "C1") (pin "2") (pinfunction "2_2") (pintype "passive"))
      (node (ref "C13") (pin "+") (pinfunction "+_+") (pintype "passive"))
      (node (ref "C30") (pin "1") (pinfunction "1_1") (pintype "passive"))
      (node (ref "D1") (pin "C") (pinfunction "C_C") (pintype "passive"))
      (node (ref "D2") (pin "A") (pinfunction "A_A") (pintype "passive"))
      (node (ref "HEADR4") (pin "1") (pinfunction "1_1") (pintype "passive"))
      (node (ref "IC2") (pin "1") (pinfunction "OUT_1") (pintype "output"))
      (node (ref "R1") (pin "1") (pinfunction "1_1") (pintype "passive"))
      (node (ref "R10") (pin "1") (pinfunction "1_1") (pintype "passive"))
    )
    (net (code "56") (name "TO_RESO_POT2") (class "Default")
      (node (ref "HEADR4") (pin "2") (pinfunction "2_2") (pintype "passive"))
      (node (ref "IC3") (pin "3") (pinfunction "+IN_3") (pintype "input"))
      (node (ref "R11") (pin "2") (pinfunction "2_2") (pintype "passive"))
    )
    (net (code "57") (name "V+") (class "Default")
      (node (ref "C15") (pin "+") (pinfunction "+_+") (pintype "passive"))
      (node (ref "C17") (pin "2") (pinfunction "2_2") (pintype "passive"))
      (node (ref "C19") (pin "2") (pinfunction "2_2") (pintype "passive"))
      (node (ref "C21") (pin "2") (pinfunction "2_2") (pintype "passive"))
      (node (ref "C23") (pin "2") (pinfunction "2_2") (pintype "passive"))
      (node (ref "C27") (pin "2") (pinfunction "2_2") (pintype "passive"))
      (node (ref "IC1") (pin "16") (pinfunction "V+_16") (pintype "power_in"))
      (node (ref "IC2") (pin "8") (pinfunction "P$V+_8") (pintype "bidirectional"))
      (node (ref "IC3") (pin "8") (pinfunction "P$V+_8") (pintype "bidirectional"))
      (node (ref "IC4") (pin "8") (pinfunction "P$V+_8") (pintype "bidirectional"))
      (node (ref "IC5") (pin "8") (pinfunction "P$V+_8") (pintype "bidirectional"))
      (node (ref "IC6") (pin "8") (pinfunction "P$V+_8") (pintype "bidirectional"))
      (node (ref "L1") (pin "1") (pinfunction "1_1") (pintype "passive"))
    )
    (net (code "58") (name "V-") (class "Default")
      (node (ref "C16") (pin "-") (pinfunction "-_-") (pintype "passive"))
      (node (ref "C18") (pin "1") (pinfunction "1_1") (pintype "passive"))
      (node (ref "C20") (pin "1") (pinfunction "1_1") (pintype "passive"))
      (node (ref "C22") (pin "1") (pinfunction "1_1") (pintype "passive"))
      (node (ref "C24") (pin "1") (pinfunction "1_1") (pintype "passive"))
      (node (ref "C28") (pin "1") (pinfunction "1_1") (pintype "passive"))
      (node (ref "D7") (pin "A") (pinfunction "A_A") (pintype "passive"))
      (node (ref "IC1") (pin "9") (pinfunction "V-_9") (pintype "power_in"))
      (node (ref "IC2") (pin "4") (pinfunction "P$V-_4") (pintype "bidirectional"))
      (node (ref "IC3") (pin "4") (pinfunction "P$V-_4") (pintype "bidirectional"))
      (node (ref "IC4") (pin "4") (pinfunction "P$V-_4") (pintype "bidirectional"))
      (node (ref "IC5") (pin "4") (pinfunction "P$V-_4") (pintype "bidirectional"))
      (node (ref "IC6") (pin "4") (pinfunction "P$V-_4") (pintype "bidirectional"))
      (node (ref "L2") (pin "1") (pinfunction "1_1") (pintype "passive"))
      (node (ref "R16") (pin "2") (pinfunction "2_2") (pintype "passive"))
    )
    (net (code "59") (name "unconnected-(IC1C-CTRL-Pad11)") (class "Default")
      (node (ref "IC1") (pin "11") (pinfunction "CTRL_11") (pintype "input"))
    )
    (net (code "60") (name "unconnected-(IC1C-IN-Pad10)") (class "Default")
      (node (ref "IC1") (pin "10") (pinfunction "IN_10") (pintype "input"))
    )
    (net (code "61") (name "unconnected-(IC1C-OUT-Pad12)") (class "Default")
      (node (ref "IC1") (pin "12") (pinfunction "OUT_12") (pintype "output"))
    )
    (net (code "62") (name "unconnected-(IC1D-CTRL-Pad14)") (class "Default")
      (node (ref "IC1") (pin "14") (pinfunction "CTRL_14") (pintype "input"))
    )
    (net (code "63") (name "unconnected-(IC1D-IN-Pad15)") (class "Default")
      (node (ref "IC1") (pin "15") (pinfunction "IN_15") (pintype "input"))
    )
    (net (code "64") (name "unconnected-(IC1D-OUT-Pad13)") (class "Default")
      (node (ref "IC1") (pin "13") (pinfunction "OUT_13") (pintype "output"))
    )
    (net (code "65") (name "unconnected-(IC1E-MODE-Pad1)") (class "Default")
      (node (ref "IC1") (pin "1") (pinfunction "MODE_1") (pintype "input"))
    )
  )
)
